# Stepper.net
KiCad netlist of a schematic drawn in EAGLE
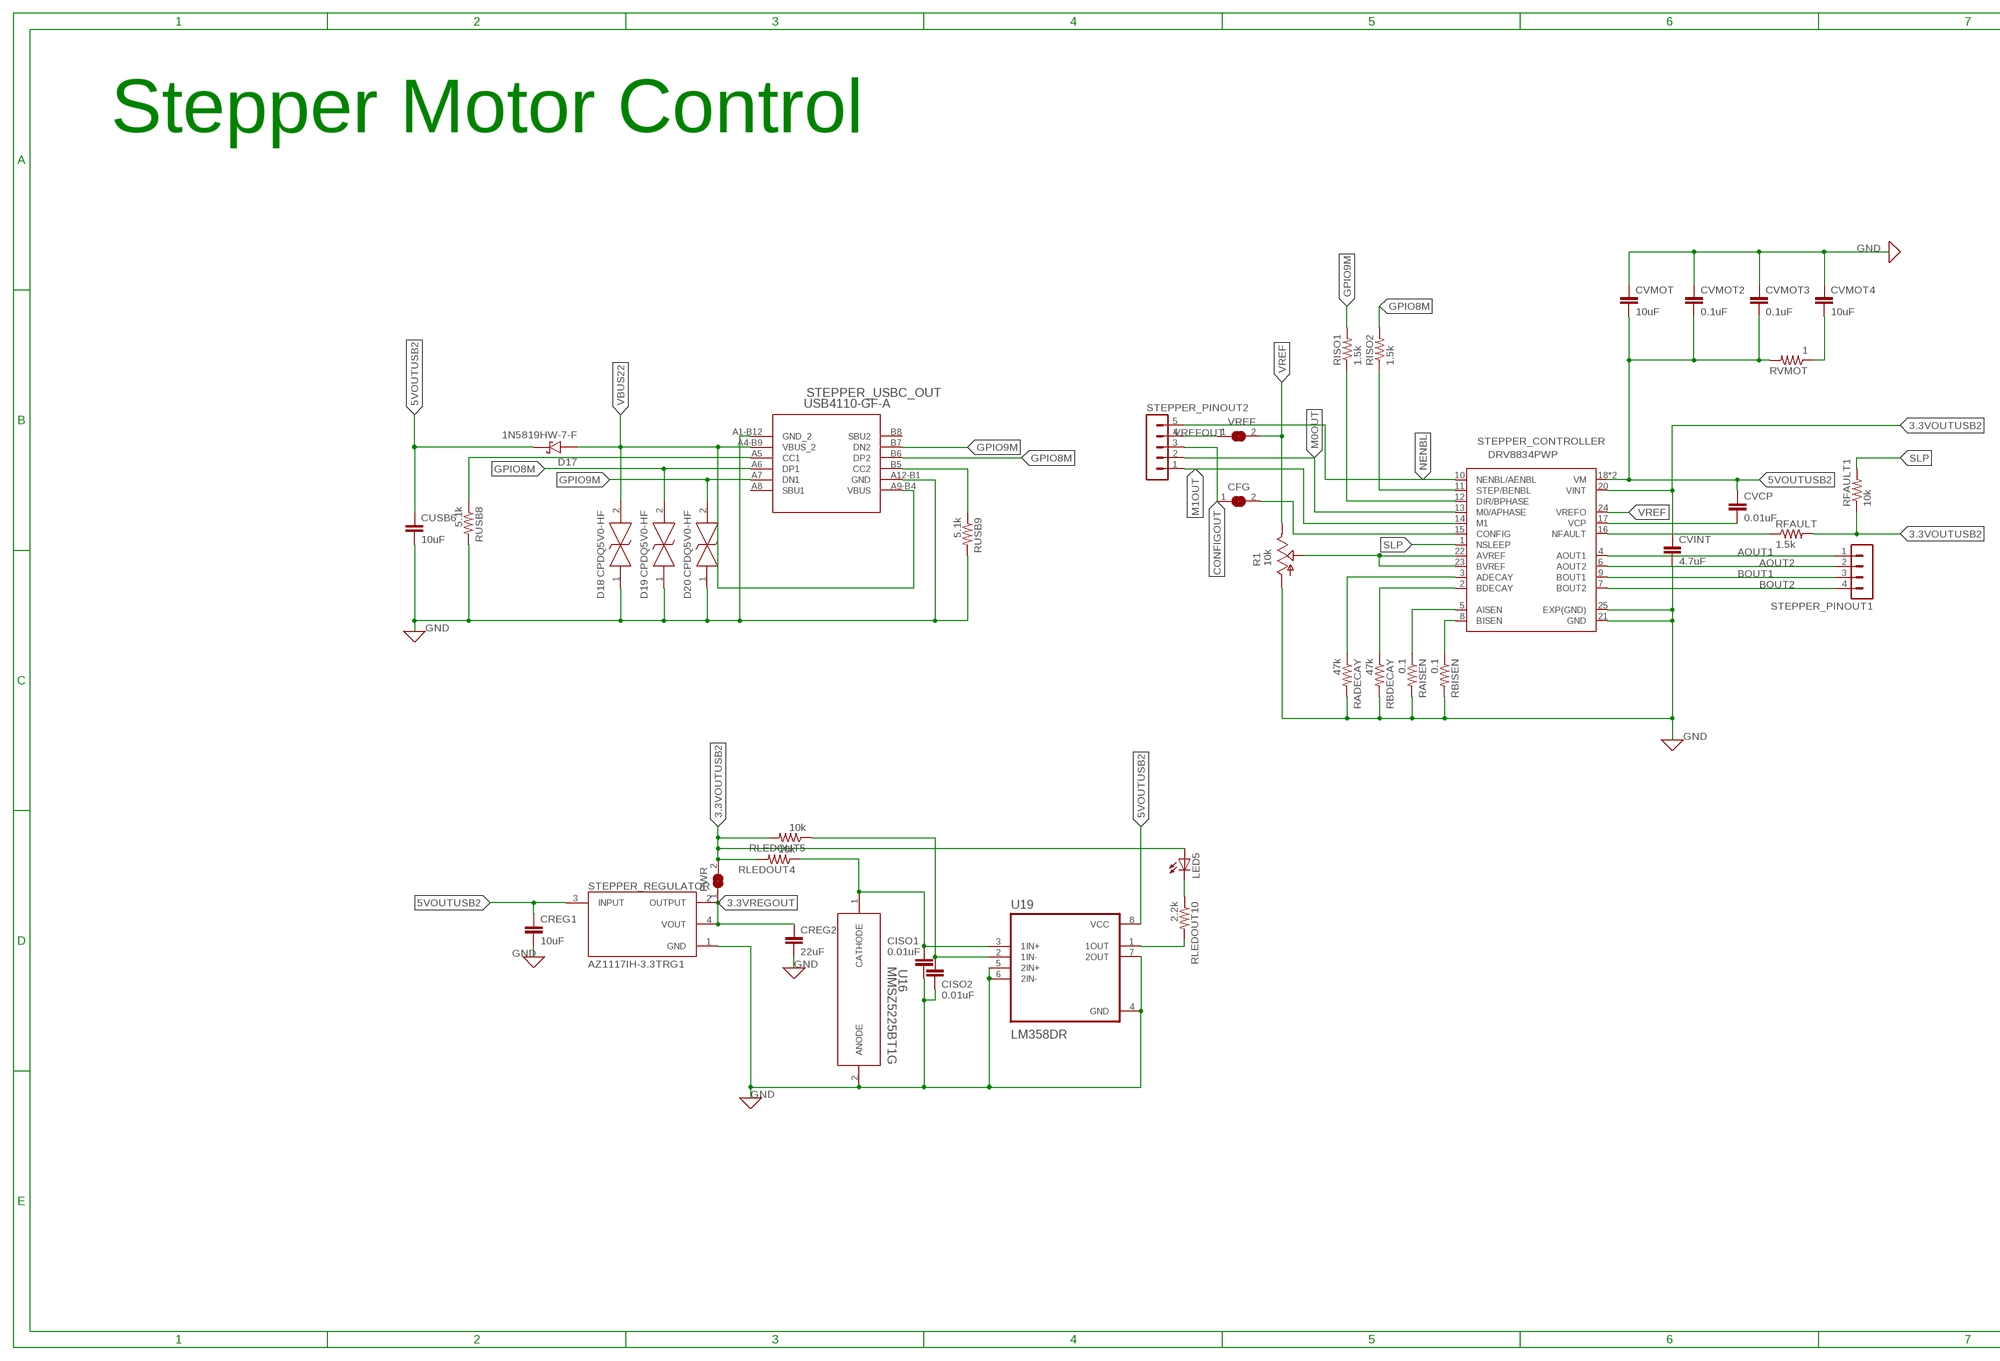
[diagram p0: schematic, sheet 1, part 1 of 2]
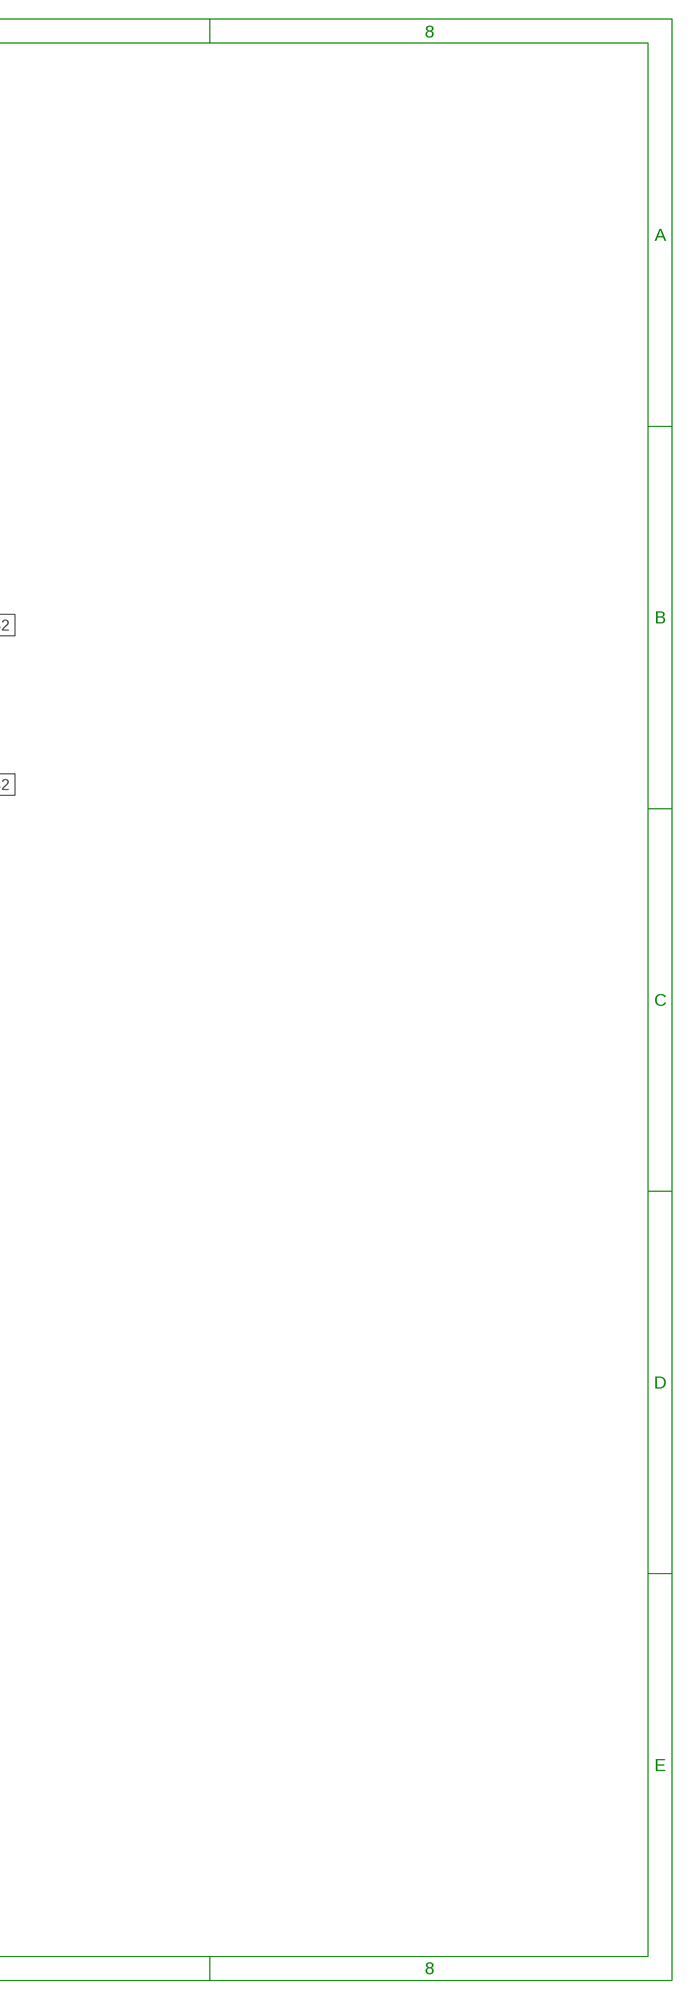
[diagram p1: schematic, sheet 1, part 2 of 2]

(export (version "E")
  (design (tool "Eeschema 10.0.6"))
  (components
    (comp (ref "CFG") (value "SJ") (footprint "eagle-import:SJ") (libsource (lib "eagle-import") (part "SJ")))
    (comp (ref "CISO1")
      (value "0.01uF")
      (footprint "eagle-import:C0805")
      (libsource (lib "eagle-import") (part "C-EUC0805"))
    )
    (comp (ref "CISO2")
      (value "0.01uF")
      (footprint "eagle-import:C0805")
      (libsource (lib "eagle-import") (part "C-EUC0805"))
    )
    (comp (ref "CREG1")
      (value "10uF")
      (footprint "eagle-import:C0805")
      (libsource (lib "eagle-import") (part "C-EUC0805"))
    )
    (comp (ref "CREG2")
      (value "22uF")
      (footprint "eagle-import:C0805")
      (libsource (lib "eagle-import") (part "C-EUC0805"))
    )
    (comp (ref "CUSB6")
      (value "10uF")
      (footprint "eagle-import:C0805")
      (libsource (lib "eagle-import") (part "C-EUC0805"))
    )
    (comp (ref "CVCP")
      (value "0.01uF")
      (footprint "eagle-import:C0805")
      (libsource (lib "eagle-import") (part "C-EUC0805"))
    )
    (comp (ref "CVINT")
      (value "4.7uF")
      (footprint "eagle-import:C0805")
      (libsource (lib "eagle-import") (part "C-EUC0805"))
    )
    (comp (ref "CVMOT")
      (value "10uF")
      (footprint "eagle-import:C0805")
      (libsource (lib "eagle-import") (part "C-EUC0805"))
    )
    (comp (ref "CVMOT2")
      (value "0.1uF")
      (footprint "eagle-import:C0805")
      (libsource (lib "eagle-import") (part "C-EUC0805"))
    )
    (comp (ref "CVMOT3")
      (value "0.1uF")
      (footprint "eagle-import:C0805")
      (libsource (lib "eagle-import") (part "C-EUC0805"))
    )
    (comp (ref "CVMOT4")
      (value "10uF")
      (footprint "eagle-import:C0805")
      (libsource (lib "eagle-import") (part "C-EUC0805"))
    )
    (comp (ref "D17")
      (value "1N5819HW-7-F")
      (footprint "eagle-import:SOD3715X145N")
      (fields (field (name "MF") "Diodes Inc."))
      (libsource (lib "eagle-import") (part "1N5819HW-7-F"))
    )
    (comp (ref "D18")
      (value "CPDQ5V0-HF")
      (footprint "eagle-import:MBTB-D-SOD-923F-IMP-0402")
      (fields (field (name "MF") "Comchip Technology"))
      (libsource (lib "eagle-import") (part "CPDQ5V0-HF"))
    )
    (comp (ref "D19")
      (value "CPDQ5V0-HF")
      (footprint "eagle-import:MBTB-D-SOD-923F-IMP-0402")
      (fields (field (name "MF") "Comchip Technology"))
      (libsource (lib "eagle-import") (part "CPDQ5V0-HF"))
    )
    (comp (ref "D20")
      (value "CPDQ5V0-HF")
      (footprint "eagle-import:MBTB-D-SOD-923F-IMP-0402")
      (fields (field (name "MF") "Comchip Technology"))
      (libsource (lib "eagle-import") (part "CPDQ5V0-HF"))
    )
    (comp (ref "LED5")
      (value "LED")
      (footprint "eagle-import:SMARTLED-TTW")
      (libsource (lib "eagle-import") (part "LED"))
    )
    (comp (ref "PWR") (value "SJ") (footprint "eagle-import:SJ") (libsource (lib "eagle-import") (part "SJ")))
    (comp (ref "R1")
      (value "10k")
      (footprint "eagle-import:3223G")
      (libsource (lib "eagle-import") (part "TRIM_US-3223G"))
    )
    (comp (ref "RADECAY")
      (value "47k")
      (footprint "eagle-import:M0805")
      (libsource (lib "eagle-import") (part "R-US_M0805"))
    )
    (comp (ref "RAISEN")
      (value "0.1")
      (footprint "eagle-import:M0805")
      (libsource (lib "eagle-import") (part "R-US_M0805"))
    )
    (comp (ref "RBDECAY")
      (value "47k")
      (footprint "eagle-import:M0805")
      (libsource (lib "eagle-import") (part "R-US_M0805"))
    )
    (comp (ref "RBISEN")
      (value "0.1")
      (footprint "eagle-import:M0805")
      (libsource (lib "eagle-import") (part "R-US_M0805"))
    )
    (comp (ref "RFAULT")
      (value "1.5k")
      (footprint "eagle-import:M0805")
      (libsource (lib "eagle-import") (part "R-US_M0805"))
    )
    (comp (ref "RFAULT1")
      (value "10k")
      (footprint "eagle-import:M0805")
      (libsource (lib "eagle-import") (part "R-US_M0805"))
    )
    (comp (ref "RISO1")
      (value "1.5k")
      (footprint "eagle-import:M0805")
      (libsource (lib "eagle-import") (part "R-US_M0805"))
    )
    (comp (ref "RISO2")
      (value "1.5k")
      (footprint "eagle-import:M0805")
      (libsource (lib "eagle-import") (part "R-US_M0805"))
    )
    (comp (ref "RLEDOUT4")
      (value "10k")
      (footprint "eagle-import:M0805")
      (libsource (lib "eagle-import") (part "R-US_M0805"))
    )
    (comp (ref "RLEDOUT5")
      (value "10k")
      (footprint "eagle-import:M0805")
      (libsource (lib "eagle-import") (part "R-US_M0805"))
    )
    (comp (ref "RLEDOUT10")
      (value "2.2k")
      (footprint "eagle-import:M0805")
      (libsource (lib "eagle-import") (part "R-US_M0805"))
    )
    (comp (ref "RUSB8")
      (value "5.1k")
      (footprint "eagle-import:M0805")
      (libsource (lib "eagle-import") (part "R-US_M0805"))
    )
    (comp (ref "RUSB9")
      (value "5.1k")
      (footprint "eagle-import:M0805")
      (libsource (lib "eagle-import") (part "R-US_M0805"))
    )
    (comp (ref "RVMOT")
      (value "1")
      (footprint "eagle-import:M0805")
      (libsource (lib "eagle-import") (part "R-US_M0805"))
    )
    (comp (ref "STEPPER_CONTROLLER")
      (value "DRV8834PWP")
      (footprint "eagle-import:SOP65P640X120-25N")
      (fields (field (name "MF") "Texas Instruments"))
      (libsource (lib "eagle-import") (part "DRV8834PWP"))
    )
    (comp (ref "STEPPER_PINOUT1")
      (value "MA04-1")
      (footprint "eagle-import:MA04-1")
      (libsource (lib "eagle-import") (part "MA04-1"))
    )
    (comp (ref "STEPPER_PINOUT2")
      (value "MA05-1")
      (footprint "eagle-import:MA05-1")
      (libsource (lib "eagle-import") (part "MA05-1"))
    )
    (comp (ref "STEPPER_REGULATOR")
      (value "AZ1117IH-3.3TRG1")
      (footprint "eagle-import:SOT230P700X185-4N")
      (fields (field (name "MF") "Diodes Inc."))
      (libsource (lib "eagle-import") (part "AZ1117IH-3.3TRG1"))
    )
    (comp (ref "STEPPER_USBC_OUT")
      (value "USB4110-GF-A")
      (footprint "eagle-import:USB4110-GF-A_GCT")
      (fields (field (name "COPYRIGHT") "Copyright (C) 2023 Ultra Librarian. All rights reserved."))
      (libsource (lib "eagle-import") (part "USB4110-GF-A"))
    )
    (comp (ref "U16")
      (value "MMSZ5225BT1G")
      (footprint "eagle-import:SOD-123_ONS")
      (fields (field (name "COPYRIGHT") "Copyright (C) 2023 Ultra Librarian. All rights reserved."))
      (libsource (lib "eagle-import") (part "MMSZ5225BT1G"))
    )
    (comp (ref "U19")
      (value "LM358DR")
      (footprint "eagle-import:SOIC127P599X175-8N")
      (fields (field (name "MF") "Texas Instruments"))
      (libsource (lib "eagle-import") (part "LM358DR"))
    )
    (comp (ref "VREF")
      (value "SJ")
      (footprint "eagle-import:SJ")
      (libsource (lib "eagle-import") (part "SJ"))
    )
  )
  (nets
    (net (code "1") (name "/AOUT1") (class "Default")
      (node (ref "STEPPER_CONTROLLER") (pin "4") (pinfunction "AOUT1_4") (pintype "output"))
      (node (ref "STEPPER_PINOUT1") (pin "1") (pinfunction "1_1") (pintype "passive"))
    )
    (net (code "2") (name "/AOUT2") (class "Default")
      (node (ref "STEPPER_CONTROLLER") (pin "6") (pinfunction "AOUT2_6") (pintype "output"))
      (node (ref "STEPPER_PINOUT1") (pin "2") (pinfunction "2_2") (pintype "passive"))
    )
    (net (code "3") (name "/BOUT1") (class "Default")
      (node (ref "STEPPER_CONTROLLER") (pin "9") (pinfunction "BOUT1_9") (pintype "output"))
      (node (ref "STEPPER_PINOUT1") (pin "3") (pinfunction "3_3") (pintype "passive"))
    )
    (net (code "4") (name "/BOUT2") (class "Default")
      (node (ref "STEPPER_CONTROLLER") (pin "7") (pinfunction "BOUT2_7") (pintype "output"))
      (node (ref "STEPPER_PINOUT1") (pin "4") (pinfunction "4_4") (pintype "passive"))
    )
    (net (code "5") (name "/VREFOUT") (class "Default")
      (node (ref "STEPPER_PINOUT2") (pin "4") (pinfunction "4_4") (pintype "passive"))
      (node (ref "VREF") (pin "1") (pinfunction "1_1") (pintype "passive"))
    )
    (net (code "6") (name "3.3VOUTUSB2") (class "Default")
      (node (ref "CVINT") (pin "1") (pinfunction "1_1") (pintype "passive"))
      (node (ref "LED5") (pin "A@1") (pinfunction "A_A@1") (pintype "passive"))
      (node (ref "PWR") (pin "2") (pinfunction "2_2") (pintype "passive"))
      (node (ref "RFAULT") (pin "2") (pinfunction "2_2") (pintype "passive"))
      (node (ref "RFAULT1") (pin "1") (pinfunction "1_1") (pintype "passive"))
      (node (ref "RLEDOUT4") (pin "2") (pinfunction "2_2") (pintype "passive"))
      (node (ref "RLEDOUT5") (pin "2") (pinfunction "2_2") (pintype "passive"))
      (node (ref "STEPPER_CONTROLLER") (pin "20") (pinfunction "VINT_20") (pintype "power_in"))
    )
    (net (code "7") (name "3.3VREGOUT") (class "Default")
      (node (ref "CREG2") (pin "1") (pinfunction "1_1") (pintype "passive"))
      (node (ref "PWR") (pin "1") (pinfunction "1_1") (pintype "passive"))
      (node (ref "STEPPER_REGULATOR") (pin "2") (pinfunction "OUTPUT_2") (pintype "output"))
      (node (ref "STEPPER_REGULATOR") (pin "4") (pinfunction "VOUT_4") (pintype "output"))
    )
    (net (code "8") (name "5VOUTUSB2") (class "Default")
      (node (ref "CREG1") (pin "1") (pinfunction "1_1") (pintype "passive"))
      (node (ref "CUSB6") (pin "1") (pinfunction "1_1") (pintype "passive"))
      (node (ref "CVCP") (pin "1") (pinfunction "1_1") (pintype "passive"))
      (node (ref "CVMOT") (pin "2") (pinfunction "2_2") (pintype "passive"))
      (node (ref "CVMOT2") (pin "2") (pinfunction "2_2") (pintype "passive"))
      (node (ref "CVMOT3") (pin "2") (pinfunction "2_2") (pintype "passive"))
      (node (ref "D17") (pin "C") (pinfunction "K_C") (pintype "passive"))
      (node (ref "RVMOT") (pin "2") (pinfunction "2_2") (pintype "passive"))
      (node (ref "STEPPER_CONTROLLER") (pin "18") (pinfunction "VM_18") (pintype "power_in"))
      (node (ref "STEPPER_CONTROLLER") (pin "19") (pinfunction "VM_19") (pintype "power_in"))
      (node (ref "STEPPER_REGULATOR") (pin "3") (pinfunction "INPUT_3") (pintype "input"))
      (node (ref "U19") (pin "8") (pinfunction "VCC_8") (pintype "power_in"))
    )
    (net (code "9") (name "CONFIGOUT") (class "Default")
      (node (ref "CFG") (pin "1") (pinfunction "1_1") (pintype "passive"))
      (node (ref "STEPPER_PINOUT2") (pin "3") (pinfunction "3_3") (pintype "passive"))
    )
    (net (code "10") (name "GND") (class "Default")
      (node (ref "CISO1") (pin "2") (pinfunction "2_2") (pintype "passive"))
      (node (ref "CISO2") (pin "2") (pinfunction "2_2") (pintype "passive"))
      (node (ref "CREG1") (pin "2") (pinfunction "2_2") (pintype "passive"))
      (node (ref "CREG2") (pin "2") (pinfunction "2_2") (pintype "passive"))
      (node (ref "CUSB6") (pin "2") (pinfunction "2_2") (pintype "passive"))
      (node (ref "CVINT") (pin "2") (pinfunction "2_2") (pintype "passive"))
      (node (ref "CVMOT") (pin "1") (pinfunction "1_1") (pintype "passive"))
      (node (ref "CVMOT2") (pin "1") (pinfunction "1_1") (pintype "passive"))
      (node (ref "CVMOT3") (pin "1") (pinfunction "1_1") (pintype "passive"))
      (node (ref "CVMOT4") (pin "1") (pinfunction "1_1") (pintype "passive"))
      (node (ref "D18") (pin "1") (pinfunction "K_1") (pintype "bidirectional"))
      (node (ref "D19") (pin "1") (pinfunction "K_1") (pintype "bidirectional"))
      (node (ref "D20") (pin "1") (pinfunction "K_1") (pintype "bidirectional"))
      (node (ref "R1") (pin "1") (pinfunction "A_1") (pintype "passive"))
      (node (ref "RADECAY") (pin "2") (pinfunction "2_2") (pintype "passive"))
      (node (ref "RAISEN") (pin "2") (pinfunction "2_2") (pintype "passive"))
      (node (ref "RBDECAY") (pin "2") (pinfunction "2_2") (pintype "passive"))
      (node (ref "RBISEN") (pin "2") (pinfunction "2_2") (pintype "passive"))
      (node (ref "RUSB8") (pin "2") (pinfunction "2_2") (pintype "passive"))
      (node (ref "RUSB9") (pin "2") (pinfunction "2_2") (pintype "passive"))
      (node (ref "STEPPER_CONTROLLER") (pin "21") (pinfunction "GND_21") (pintype "power_in"))
      (node (ref "STEPPER_CONTROLLER") (pin "25") (pinfunction "EXP(GND)_25") (pintype "power_in"))
      (node (ref "STEPPER_REGULATOR") (pin "1") (pinfunction "GND_1") (pintype "power_in"))
      (node (ref "STEPPER_USBC_OUT") (pin "A1-B12") (pinfunction "GND_2_A1-B12") (pintype "passive"))
      (node (ref "STEPPER_USBC_OUT") (pin "A12-B1") (pinfunction "GND_A12-B1") (pintype "passive"))
      (node (ref "U16") (pin "2") (pinfunction "ANODE_2") (pintype "passive"))
      (node (ref "U19") (pin "4") (pinfunction "GND_4") (pintype "power_in"))
      (node (ref "U19") (pin "5") (pinfunction "2IN+_5") (pintype "input"))
      (node (ref "U19") (pin "6") (pinfunction "2IN-_6") (pintype "input"))
      (node (ref "U19") (pin "7") (pinfunction "2OUT_7") (pintype "output"))
    )
    (net (code "11") (name "GPIO8M") (class "Default")
      (node (ref "D19") (pin "2") (pinfunction "A_2") (pintype "bidirectional"))
      (node (ref "RISO2") (pin "2") (pinfunction "2_2") (pintype "passive"))
      (node (ref "STEPPER_USBC_OUT") (pin "A6") (pinfunction "DP1_A6") (pintype "bidirectional"))
      (node (ref "STEPPER_USBC_OUT") (pin "B6") (pinfunction "DP2_B6") (pintype "bidirectional"))
    )
    (net (code "12") (name "GPIO9M") (class "Default")
      (node (ref "D20") (pin "2") (pinfunction "A_2") (pintype "bidirectional"))
      (node (ref "RISO1") (pin "2") (pinfunction "2_2") (pintype "passive"))
      (node (ref "STEPPER_USBC_OUT") (pin "A7") (pinfunction "DN1_A7") (pintype "bidirectional"))
      (node (ref "STEPPER_USBC_OUT") (pin "B7") (pinfunction "DN2_B7") (pintype "bidirectional"))
    )
    (net (code "13") (name "M0OUT") (class "Default")
      (node (ref "STEPPER_CONTROLLER") (pin "13") (pinfunction "M0/APHASE_13") (pintype "input"))
      (node (ref "STEPPER_PINOUT2") (pin "2") (pinfunction "2_2") (pintype "passive"))
    )
    (net (code "14") (name "M1OUT") (class "Default")
      (node (ref "STEPPER_CONTROLLER") (pin "14") (pinfunction "M1_14") (pintype "input"))
      (node (ref "STEPPER_PINOUT2") (pin "1") (pinfunction "1_1") (pintype "passive"))
    )
    (net (code "15") (name "NENBL") (class "Default")
      (node (ref "STEPPER_CONTROLLER") (pin "10") (pinfunction "NENBL/AENBL_10") (pintype "input"))
      (node (ref "STEPPER_PINOUT2") (pin "5") (pinfunction "5_5") (pintype "passive"))
    )
    (net (code "16") (name "Net-(CVMOT4-Pad2)") (class "Default")
      (node (ref "CVMOT4") (pin "2") (pinfunction "2_2") (pintype "passive"))
      (node (ref "RVMOT") (pin "1") (pinfunction "1_1") (pintype "passive"))
    )
    (net (code "17") (name "Net-(LED5-C)") (class "Default")
      (node (ref "LED5") (pin "C@1") (pinfunction "C_C@1") (pintype "passive"))
      (node (ref "RLEDOUT10") (pin "1") (pinfunction "1_1") (pintype "passive"))
    )
    (net (code "18") (name "Net-(R1-S)") (class "Default")
      (node (ref "R1") (pin "2") (pinfunction "S_2") (pintype "passive"))
      (node (ref "STEPPER_CONTROLLER") (pin "22") (pinfunction "AVREF_22") (pintype "input"))
      (node (ref "STEPPER_CONTROLLER") (pin "23") (pinfunction "BVREF_23") (pintype "input"))
    )
    (net (code "19") (name "Net-(STEPPER_CONTROLLER-ADECAY)") (class "Default")
      (node (ref "RADECAY") (pin "1") (pinfunction "1_1") (pintype "passive"))
      (node (ref "STEPPER_CONTROLLER") (pin "3") (pinfunction "ADECAY_3") (pintype "input"))
    )
    (net (code "20") (name "Net-(STEPPER_CONTROLLER-AISEN)") (class "Default")
      (node (ref "RAISEN") (pin "1") (pinfunction "1_1") (pintype "passive"))
      (node (ref "STEPPER_CONTROLLER") (pin "5") (pinfunction "AISEN_5") (pintype "bidirectional"))
    )
    (net (code "21") (name "Net-(STEPPER_CONTROLLER-BDECAY)") (class "Default")
      (node (ref "RBDECAY") (pin "1") (pinfunction "1_1") (pintype "passive"))
      (node (ref "STEPPER_CONTROLLER") (pin "2") (pinfunction "BDECAY_2") (pintype "input"))
    )
    (net (code "22") (name "Net-(STEPPER_CONTROLLER-BISEN)") (class "Default")
      (node (ref "RBISEN") (pin "1") (pinfunction "1_1") (pintype "passive"))
      (node (ref "STEPPER_CONTROLLER") (pin "8") (pinfunction "BISEN_8") (pintype "bidirectional"))
    )
    (net (code "23") (name "Net-(STEPPER_CONTROLLER-CONFIG)") (class "Default")
      (node (ref "CFG") (pin "2") (pinfunction "2_2") (pintype "passive"))
      (node (ref "STEPPER_CONTROLLER") (pin "15") (pinfunction "CONFIG_15") (pintype "input"))
    )
    (net (code "24") (name "Net-(STEPPER_CONTROLLER-DIR{slash}BPHASE)") (class "Default")
      (node (ref "RISO1") (pin "1") (pinfunction "1_1") (pintype "passive"))
      (node (ref "STEPPER_CONTROLLER") (pin "12") (pinfunction "DIR/BPHASE_12") (pintype "input"))
    )
    (net (code "25") (name "Net-(STEPPER_CONTROLLER-NFAULT)") (class "Default")
      (node (ref "RFAULT") (pin "1") (pinfunction "1_1") (pintype "passive"))
      (node (ref "STEPPER_CONTROLLER") (pin "16") (pinfunction "NFAULT_16") (pintype "output"))
    )
    (net (code "26") (name "Net-(STEPPER_CONTROLLER-STEP{slash}BENBL)") (class "Default")
      (node (ref "RISO2") (pin "1") (pinfunction "1_1") (pintype "passive"))
      (node (ref "STEPPER_CONTROLLER") (pin "11") (pinfunction "STEP/BENBL_11") (pintype "input"))
    )
    (net (code "27") (name "Net-(STEPPER_CONTROLLER-VCP)") (class "Default")
      (node (ref "CVCP") (pin "2") (pinfunction "2_2") (pintype "passive"))
      (node (ref "STEPPER_CONTROLLER") (pin "17") (pinfunction "VCP_17") (pintype "output"))
    )
    (net (code "28") (name "Net-(STEPPER_USBC_OUT-CC1)") (class "Default")
      (node (ref "RUSB8") (pin "1") (pinfunction "1_1") (pintype "passive"))
      (node (ref "STEPPER_USBC_OUT") (pin "A5") (pinfunction "CC1_A5") (pintype "bidirectional"))
    )
    (net (code "29") (name "Net-(STEPPER_USBC_OUT-CC2)") (class "Default")
      (node (ref "RUSB9") (pin "1") (pinfunction "1_1") (pintype "passive"))
      (node (ref "STEPPER_USBC_OUT") (pin "B5") (pinfunction "CC2_B5") (pintype "bidirectional"))
    )
    (net (code "30") (name "Net-(U16-CATHODE)") (class "Default")
      (node (ref "CISO1") (pin "1") (pinfunction "1_1") (pintype "passive"))
      (node (ref "RLEDOUT4") (pin "1") (pinfunction "1_1") (pintype "passive"))
      (node (ref "U16") (pin "1") (pinfunction "CATHODE_1") (pintype "passive"))
      (node (ref "U19") (pin "3") (pinfunction "1IN+_3") (pintype "input"))
    )
    (net (code "31") (name "Net-(U19-1IN-)") (class "Default")
      (node (ref "CISO2") (pin "1") (pinfunction "1_1") (pintype "passive"))
      (node (ref "RLEDOUT5") (pin "1") (pinfunction "1_1") (pintype "passive"))
      (node (ref "U19") (pin "2") (pinfunction "1IN-_2") (pintype "input"))
    )
    (net (code "32") (name "Net-(U19-1OUT)") (class "Default")
      (node (ref "RLEDOUT10") (pin "2") (pinfunction "2_2") (pintype "passive"))
      (node (ref "U19") (pin "1") (pinfunction "1OUT_1") (pintype "output"))
    )
    (net (code "33") (name "SLP") (class "Default")
      (node (ref "RFAULT1") (pin "2") (pinfunction "2_2") (pintype "passive"))
      (node (ref "STEPPER_CONTROLLER") (pin "1") (pinfunction "NSLEEP_1") (pintype "input"))
    )
    (net (code "34") (name "VBUS22") (class "Default")
      (node (ref "D17") (pin "A") (pinfunction "A_A") (pintype "passive"))
      (node (ref "D18") (pin "2") (pinfunction "A_2") (pintype "bidirectional"))
      (node (ref "STEPPER_USBC_OUT") (pin "A4-B9") (pinfunction "VBUS_2_A4-B9") (pintype "power_in"))
      (node (ref "STEPPER_USBC_OUT") (pin "A9-B4") (pinfunction "VBUS_A9-B4") (pintype "power_in"))
    )
    (net (code "35") (name "VREF") (class "Default")
      (node (ref "R1") (pin "3") (pinfunction "E_3") (pintype "passive"))
      (node (ref "STEPPER_CONTROLLER") (pin "24") (pinfunction "VREFO_24") (pintype "output"))
      (node (ref "VREF") (pin "2") (pinfunction "2_2") (pintype "passive"))
    )
    (net (code "36") (name "unconnected-(STEPPER_USBC_OUT-SBU1-PadA8)") (class "Default")
      (node (ref "STEPPER_USBC_OUT") (pin "A8") (pinfunction "SBU1_A8") (pintype "bidirectional"))
    )
    (net (code "37") (name "unconnected-(STEPPER_USBC_OUT-SBU2-PadB8)") (class "Default")
      (node (ref "STEPPER_USBC_OUT") (pin "B8") (pinfunction "SBU2_B8") (pintype "bidirectional"))
    )
  )
)
